# Sheet1.net
KiCad netlist of a schematic drawn in Altium Designer
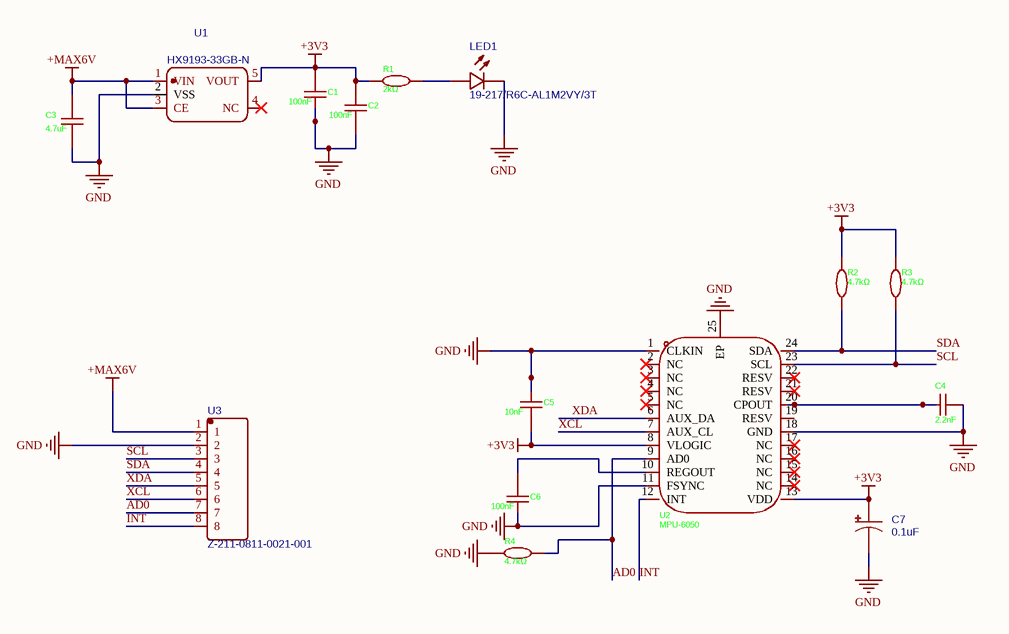
[diagram p0: Sheet1.SchDoc]

(export (version "E")
  (design (tool "Eeschema 10.0.6"))
  (components
    (comp (ref "C1")
      (value "100nF")
      (footprint "C0603")
      (fields
        (field (name "MANUFACTURER") "YAGEO(国巨)")
        (field (name "MANUFACTURER PART") "CC0603KRX7R9BB104")
        (field (name "TOLERANCE") "±10%")
      )
      (libsource (lib "Schlib1") (part "CC0603KRX7R9BB104"))
    )
    (comp (ref "C2")
      (value "100nF")
      (footprint "C0603")
      (fields
        (field (name "MANUFACTURER") "YAGEO(国巨)")
        (field (name "MANUFACTURER PART") "CC0603KRX7R9BB104")
        (field (name "TOLERANCE") "±10%")
      )
      (libsource (lib "Schlib1") (part "CC0603KRX7R9BB104"))
    )
    (comp (ref "C3")
      (value "4.7uF")
      (footprint "C0603")
      (fields
        (field (name "MANUFACTURER") "SAMSUNG(三星)")
        (field (name "MANUFACTURER PART") "CL10A475KO8NNNC")
        (field (name "TOLERANCE") "±10%")
      )
      (libsource (lib "Schlib1") (part "CL10A475KO8NNNC"))
    )
    (comp (ref "C4")
      (value "2.2nF")
      (footprint "C0805")
      (fields
        (field (name "MANUFACTURER") "SAMSUNG(三星)")
        (field (name "MANUFACTURER PART") "CL21C222JBFNNNE")
        (field (name "TOLERANCE") "±5%")
      )
      (libsource (lib "Schlib1") (part "CL21C222JBFNNNE"))
    )
    (comp (ref "C5")
      (value "10nF")
      (footprint "C0603")
      (fields
        (field (name "MANUFACTURER") "YAGEO(国巨)")
        (field (name "MANUFACTURER PART") "CC0603KRX7R9BB104")
        (field (name "TOLERANCE") "±10%")
      )
      (libsource (lib "Schlib1") (part "CC0603KRX7R9BB104"))
    )
    (comp (ref "C6")
      (value "100nF")
      (footprint "C0603")
      (fields
        (field (name "MANUFACTURER") "YAGEO(国巨)")
        (field (name "MANUFACTURER PART") "CC0603KRX7R9BB104")
        (field (name "TOLERANCE") "±10%")
      )
      (libsource (lib "Schlib1") (part "CC0603KRX7R9BB104"))
    )
    (comp (ref "C7")
      (value "0.1uF")
      (footprint "CAP-SMD_L3.2-W1.6")
      (fields
        (field (name "MANUFACTURER") "Kyocera AVX")
        (field (name "MANUFACTURER PART") "TPSA106K016R1000")
        (field (name "CONTRIBUTOR") "LCSC")
      )
      (libsource (lib "Schlib1") (part "10uF"))
    )
    (comp (ref "LED1")
      (value "19-217/R6C-AL1M2VY/3T")
      (footprint "LED0603-RD")
      (fields (field (name "MANUFACTURER") "EVERLIGHT(亿光)"))
      (libsource (lib "Schlib1") (part "19-217/R6C-AL1M2VY/3T"))
    )
    (comp (ref "R1")
      (value "2kΩ")
      (footprint "R0603")
      (fields
        (field (name "MANUFACTURER") "YAGEO(国巨)")
        (field (name "MANUFACTURER PART") "RC0603FR-072KL")
        (field (name "TOLERANCE") "±1%")
      )
      (libsource (lib "Schlib1") (part "RC0603FR-072KL"))
    )
    (comp (ref "R2")
      (value "4.7kΩ")
      (footprint "R0603")
      (fields
        (field (name "MANUFACTURER") "YAGEO(国巨)")
        (field (name "MANUFACTURER PART") "RC0603FR-074K7L")
        (field (name "TOLERANCE") "±1%")
      )
      (libsource (lib "Schlib1") (part "RC0603FR-074K7L"))
    )
    (comp (ref "R3")
      (value "4.7kΩ")
      (footprint "R0603")
      (fields
        (field (name "MANUFACTURER") "YAGEO(国巨)")
        (field (name "MANUFACTURER PART") "RC0603FR-074K7L")
        (field (name "TOLERANCE") "±1%")
      )
      (libsource (lib "Schlib1") (part "RC0603FR-074K7L"))
    )
    (comp (ref "R4")
      (value "4.7kΩ")
      (footprint "R0603")
      (fields
        (field (name "MANUFACTURER") "YAGEO(国巨)")
        (field (name "MANUFACTURER PART") "RC0603FR-074K7L")
        (field (name "TOLERANCE") "±1%")
      )
      (libsource (lib "Schlib1") (part "RC0603FR-074K7L"))
    )
    (comp (ref "U1")
      (value "HX9193-33GB-N")
      (footprint "SOT-23-5_L2.9-W1.6-P0.95-LS2.8-BL")
      (fields (field (name "MANUFACTURER") "HX(恒佳兴)") (field (name "CONTRIBUTOR") "lcsc"))
      (libsource (lib "Schlib1") (part "HX9193-33GB-N"))
    )
    (comp (ref "U2")
      (value "MPU-6050")
      (footprint "QFN-24_L4.0-W4.0-P0.50-BL-EP2.7")
      (fields (field (name "MANUFACTURER") "TDK InvenSense(应美盛)"))
      (libsource (lib "Schlib1") (part "MPU-6050"))
    )
    (comp (ref "U3")
      (value "Z-211-0811-0021-001")
      (footprint "HDR-TH_8P-P2.54-V-M")
      (fields (field (name "MANUFACTURER") "Nextron(正凌)") (field (name "CONTRIBUTOR") "LCSC"))
      (libsource (lib "Schlib1") (part "Z-211-0811-0021-001"))
    )
  )
  (nets
    (net (code "1") (name "+3V3") (class "Default")
      (node (ref "C1") (pin "2") (pinfunction "2_2") (pintype "passive"))
      (node (ref "C2") (pin "2") (pinfunction "2_2") (pintype "passive"))
      (node (ref "C5") (pin "1") (pinfunction "1_1") (pintype "passive"))
      (node (ref "C7") (pin "1") (pinfunction "1_1") (pintype "passive"))
      (node (ref "R1") (pin "1") (pinfunction "1_1") (pintype "passive"))
      (node (ref "R2") (pin "2") (pinfunction "2_2") (pintype "passive"))
      (node (ref "R3") (pin "2") (pinfunction "2_2") (pintype "passive"))
      (node (ref "U1") (pin "5") (pinfunction "VOUT_5") (pintype "passive"))
      (node (ref "U2") (pin "13") (pinfunction "VDD_13") (pintype "passive"))
      (node (ref "U2") (pin "8") (pinfunction "VLOGIC_8") (pintype "passive"))
    )
    (net (code "2") (name "+MAX6V") (class "Default")
      (node (ref "C3") (pin "2") (pinfunction "2_2") (pintype "passive"))
      (node (ref "U1") (pin "1") (pinfunction "VIN_1") (pintype "passive"))
      (node (ref "U1") (pin "3") (pinfunction "CE_3") (pintype "passive"))
      (node (ref "U3") (pin "1") (pinfunction "1_1") (pintype "passive"))
    )
    (net (code "3") (name "/AD0") (class "Default")
      (node (ref "R4") (pin "1") (pinfunction "1_1") (pintype "passive"))
      (node (ref "U2") (pin "9") (pinfunction "AD0_9") (pintype "passive"))
      (node (ref "U3") (pin "7") (pinfunction "7_7") (pintype "passive"))
    )
    (net (code "4") (name "/INT") (class "Default")
      (node (ref "U2") (pin "12") (pinfunction "INT_12") (pintype "passive"))
      (node (ref "U3") (pin "8") (pinfunction "8_8") (pintype "passive"))
    )
    (net (code "5") (name "/SCL") (class "Default")
      (node (ref "R3") (pin "1") (pinfunction "1_1") (pintype "passive"))
      (node (ref "U2") (pin "23") (pinfunction "SCL_23") (pintype "passive"))
      (node (ref "U3") (pin "3") (pinfunction "3_3") (pintype "passive"))
    )
    (net (code "6") (name "/SDA") (class "Default")
      (node (ref "R2") (pin "1") (pinfunction "1_1") (pintype "passive"))
      (node (ref "U2") (pin "24") (pinfunction "SDA_24") (pintype "passive"))
      (node (ref "U3") (pin "4") (pinfunction "4_4") (pintype "passive"))
    )
    (net (code "7") (name "/XCL") (class "Default")
      (node (ref "U2") (pin "7") (pinfunction "AUX_CL_7") (pintype "passive"))
      (node (ref "U3") (pin "6") (pinfunction "6_6") (pintype "passive"))
    )
    (net (code "8") (name "/XDA") (class "Default")
      (node (ref "U2") (pin "6") (pinfunction "AUX_DA_6") (pintype "passive"))
      (node (ref "U3") (pin "5") (pinfunction "5_5") (pintype "passive"))
    )
    (net (code "9") (name "GND") (class "Default")
      (node (ref "C1") (pin "1") (pinfunction "1_1") (pintype "passive"))
      (node (ref "C2") (pin "1") (pinfunction "1_1") (pintype "passive"))
      (node (ref "C3") (pin "1") (pinfunction "1_1") (pintype "passive"))
      (node (ref "C4") (pin "2") (pinfunction "2_2") (pintype "passive"))
      (node (ref "C5") (pin "2") (pinfunction "2_2") (pintype "passive"))
      (node (ref "C6") (pin "1") (pinfunction "1_1") (pintype "passive"))
      (node (ref "C7") (pin "2") (pinfunction "2_2") (pintype "passive"))
      (node (ref "LED1") (pin "1") (pinfunction "C_1") (pintype "passive"))
      (node (ref "R4") (pin "2") (pinfunction "2_2") (pintype "passive"))
      (node (ref "U1") (pin "2") (pinfunction "VSS_2") (pintype "passive"))
      (node (ref "U2") (pin "1") (pinfunction "CLKIN_1") (pintype "passive"))
      (node (ref "U2") (pin "11") (pinfunction "FSYNC_11") (pintype "passive"))
      (node (ref "U2") (pin "18") (pinfunction "GND_18") (pintype "passive"))
      (node (ref "U2") (pin "25") (pinfunction "EP_25") (pintype "passive"))
      (node (ref "U3") (pin "2") (pinfunction "2_2") (pintype "passive"))
    )
    (net (code "10") (name "Net-(LED1-A)") (class "Default")
      (node (ref "LED1") (pin "2") (pinfunction "A_2") (pintype "passive"))
      (node (ref "R1") (pin "2") (pinfunction "2_2") (pintype "passive"))
    )
    (net (code "11") (name "Net-(U2-CPOUT)") (class "Default")
      (node (ref "C4") (pin "1") (pinfunction "1_1") (pintype "passive"))
      (node (ref "U2") (pin "20") (pinfunction "CPOUT_20") (pintype "passive"))
    )
    (net (code "12") (name "Net-(U2-REGOUT)") (class "Default")
      (node (ref "C6") (pin "2") (pinfunction "2_2") (pintype "passive"))
      (node (ref "U2") (pin "10") (pinfunction "REGOUT_10") (pintype "passive"))
    )
    (net (code "13") (name "unconnected-(U1-NC-Pad4)") (class "Default")
      (node (ref "U1") (pin "4") (pinfunction "NC_4") (pintype "passive+no_connect"))
    )
    (net (code "14") (name "unconnected-(U2-NC-Pad2)") (class "Default")
      (node (ref "U2") (pin "2") (pinfunction "NC_2") (pintype "passive+no_connect"))
    )
    (net (code "15") (name "unconnected-(U2-NC-Pad3)") (class "Default")
      (node (ref "U2") (pin "3") (pinfunction "NC_3") (pintype "passive+no_connect"))
    )
    (net (code "16") (name "unconnected-(U2-NC-Pad4)") (class "Default")
      (node (ref "U2") (pin "4") (pinfunction "NC_4") (pintype "passive+no_connect"))
    )
    (net (code "17") (name "unconnected-(U2-NC-Pad5)") (class "Default")
      (node (ref "U2") (pin "5") (pinfunction "NC_5") (pintype "passive+no_connect"))
    )
    (net (code "18") (name "unconnected-(U2-NC-Pad14)") (class "Default")
      (node (ref "U2") (pin "14") (pinfunction "NC_14") (pintype "passive+no_connect"))
    )
    (net (code "19") (name "unconnected-(U2-NC-Pad15)") (class "Default")
      (node (ref "U2") (pin "15") (pinfunction "NC_15") (pintype "passive+no_connect"))
    )
    (net (code "20") (name "unconnected-(U2-NC-Pad16)") (class "Default")
      (node (ref "U2") (pin "16") (pinfunction "NC_16") (pintype "passive+no_connect"))
    )
    (net (code "21") (name "unconnected-(U2-NC-Pad17)") (class "Default")
      (node (ref "U2") (pin "17") (pinfunction "NC_17") (pintype "passive+no_connect"))
    )
    (net (code "22") (name "unconnected-(U2-RESV-Pad19)") (class "Default")
      (node (ref "U2") (pin "19") (pinfunction "RESV_19") (pintype "passive"))
    )
    (net (code "23") (name "unconnected-(U2-RESV-Pad21)") (class "Default")
      (node (ref "U2") (pin "21") (pinfunction "RESV_21") (pintype "passive+no_connect"))
    )
    (net (code "24") (name "unconnected-(U2-RESV-Pad22)") (class "Default")
      (node (ref "U2") (pin "22") (pinfunction "RESV_22") (pintype "passive+no_connect"))
    )
  )
)
